# HHPrototype.net
KiCad netlist of a schematic drawn in EAGLE
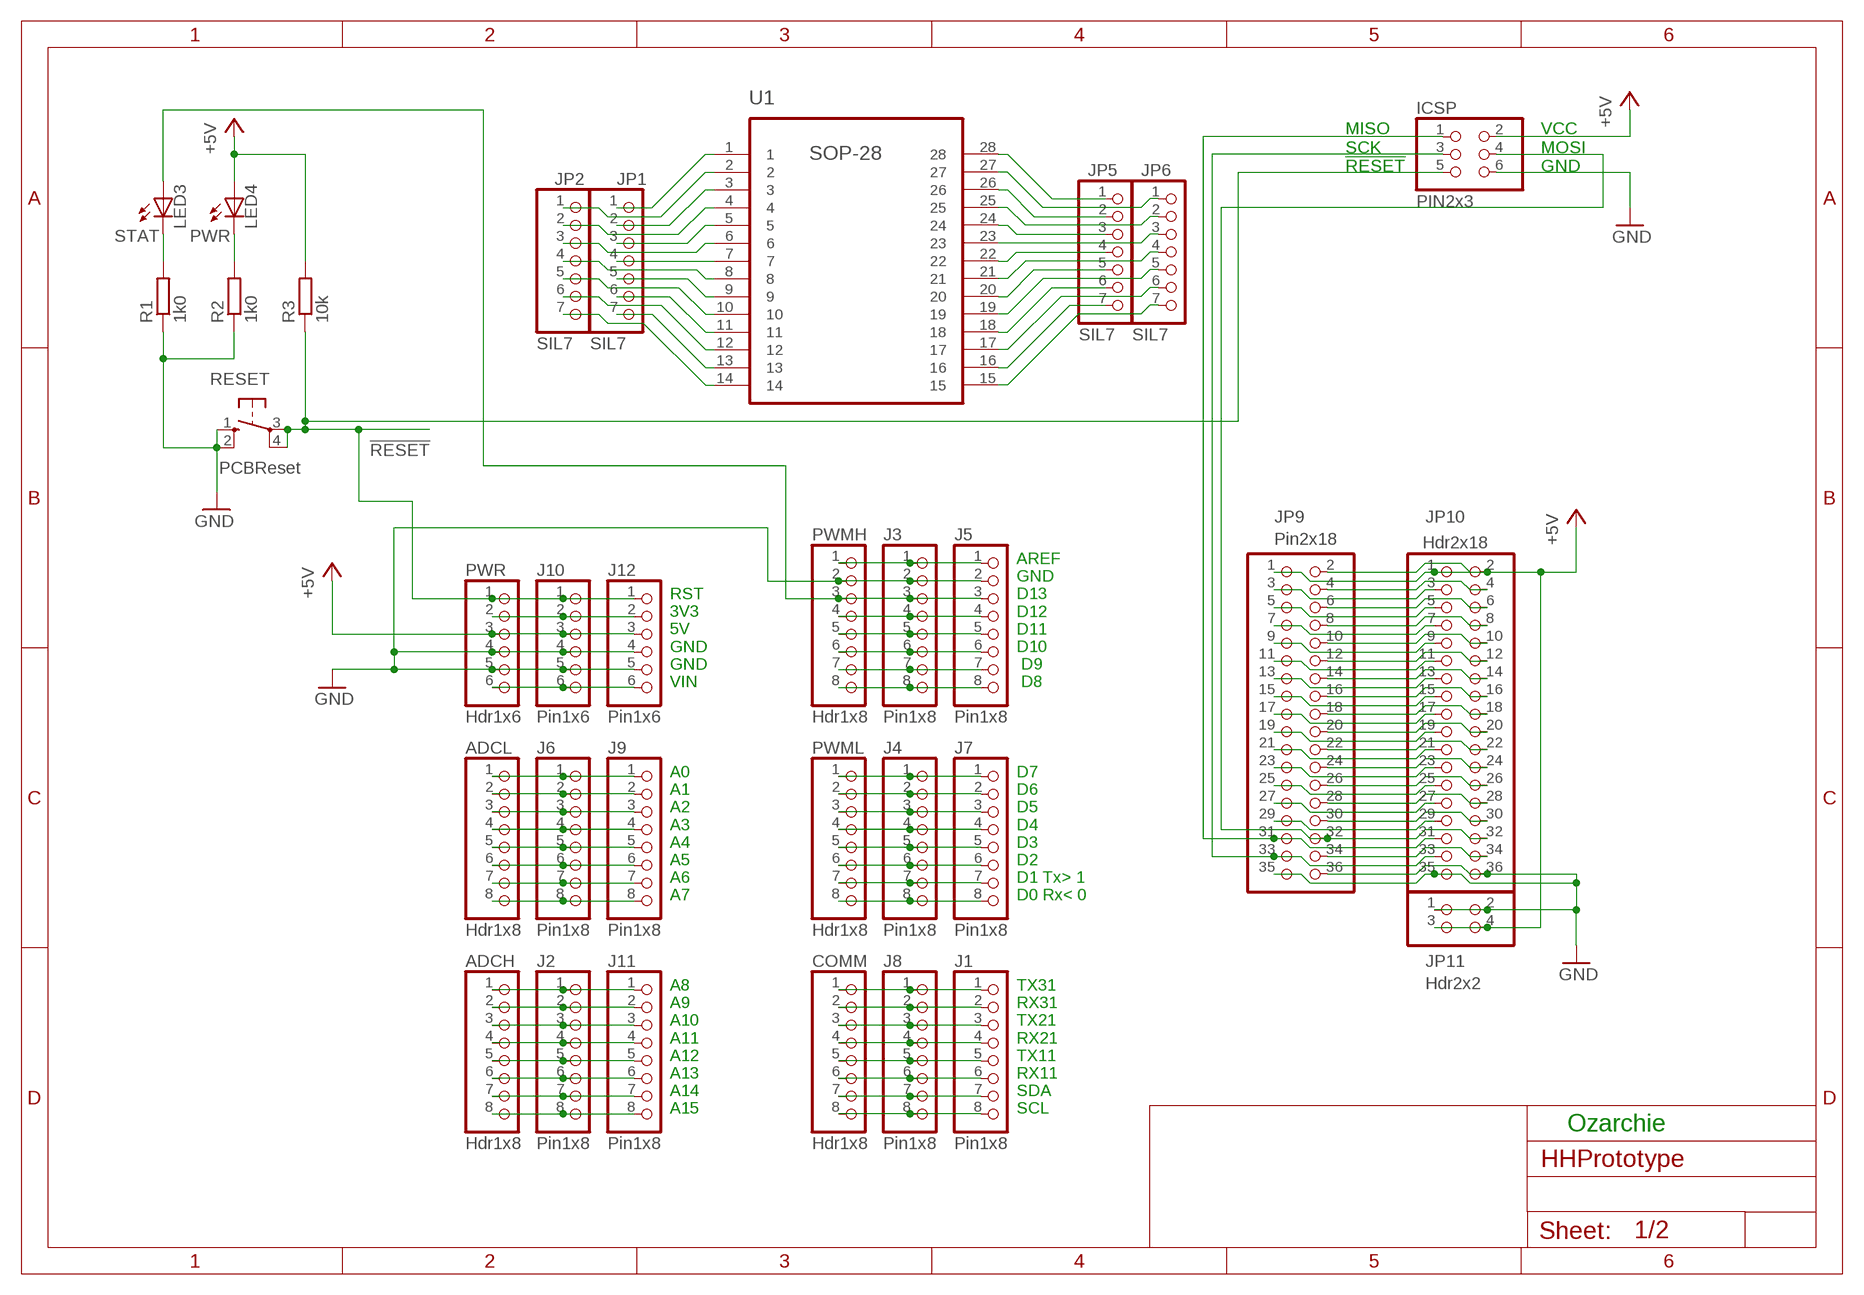
[diagram p0: schematic, sheet 1]
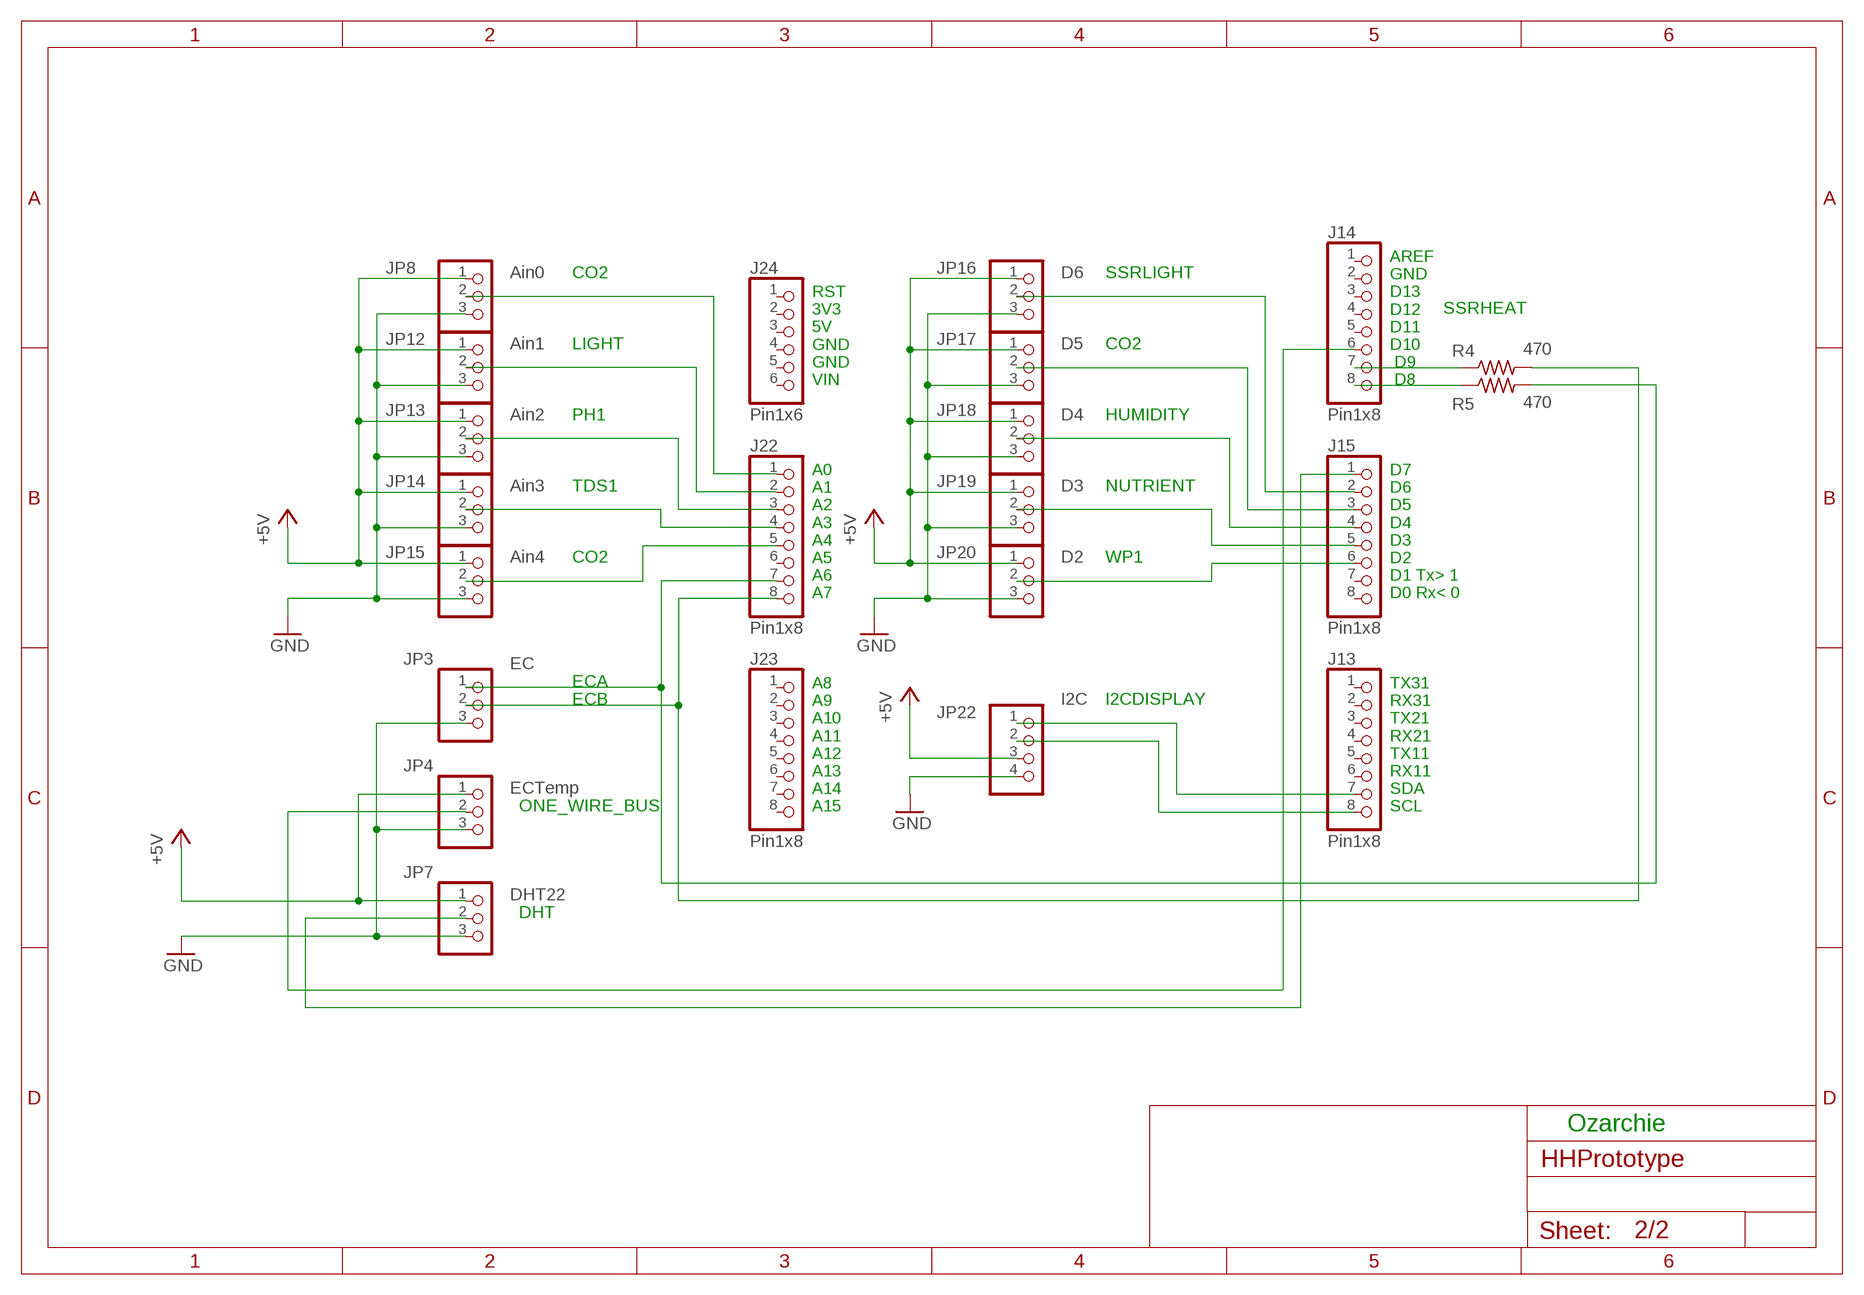
[diagram p1: schematic, sheet 2]

(export (version "E")
  (design (tool "Eeschema 10.0.6"))
  (components
    (comp (ref "ADCH")
      (value "Hdr1x8")
      (footprint "eagle-import:1X08")
      (libsource (lib "eagle-import") (part "PINHD-1X8"))
    )
    (comp (ref "ADCL")
      (value "Hdr1x8")
      (footprint "eagle-import:1X08")
      (libsource (lib "eagle-import") (part "PINHD-1X8"))
    )
    (comp (ref "COMM")
      (value "Hdr1x8")
      (footprint "eagle-import:1X08")
      (libsource (lib "eagle-import") (part "PINHD-1X8"))
    )
    (comp (ref "ICSP")
      (value "PIN2x3")
      (footprint "eagle-import:2X03")
      (libsource (lib "eagle-import") (part "PINHD-2X3"))
    )
    (comp (ref "J1")
      (value "Pin1x8")
      (footprint "eagle-import:1X08")
      (libsource (lib "eagle-import") (part "PINHD-1X8"))
    )
    (comp (ref "J2")
      (value "Pin1x8")
      (footprint "eagle-import:1X08")
      (libsource (lib "eagle-import") (part "PINHD-1X8"))
    )
    (comp (ref "J3")
      (value "Pin1x8")
      (footprint "eagle-import:1X08")
      (libsource (lib "eagle-import") (part "PINHD-1X8"))
    )
    (comp (ref "J4")
      (value "Pin1x8")
      (footprint "eagle-import:1X08")
      (libsource (lib "eagle-import") (part "PINHD-1X8"))
    )
    (comp (ref "J5")
      (value "Pin1x8")
      (footprint "eagle-import:1X08")
      (libsource (lib "eagle-import") (part "PINHD-1X8"))
    )
    (comp (ref "J6")
      (value "Pin1x8")
      (footprint "eagle-import:1X08")
      (libsource (lib "eagle-import") (part "PINHD-1X8"))
    )
    (comp (ref "J7")
      (value "Pin1x8")
      (footprint "eagle-import:1X08")
      (libsource (lib "eagle-import") (part "PINHD-1X8"))
    )
    (comp (ref "J8")
      (value "Pin1x8")
      (footprint "eagle-import:1X08")
      (libsource (lib "eagle-import") (part "PINHD-1X8"))
    )
    (comp (ref "J9")
      (value "Pin1x8")
      (footprint "eagle-import:1X08")
      (libsource (lib "eagle-import") (part "PINHD-1X8"))
    )
    (comp (ref "J10")
      (value "Pin1x6")
      (footprint "eagle-import:1X06")
      (libsource (lib "eagle-import") (part "PINHD-1X6"))
    )
    (comp (ref "J11")
      (value "Pin1x8")
      (footprint "eagle-import:1X08")
      (libsource (lib "eagle-import") (part "PINHD-1X8"))
    )
    (comp (ref "J12")
      (value "Pin1x6")
      (footprint "eagle-import:1X06")
      (libsource (lib "eagle-import") (part "PINHD-1X6"))
    )
    (comp (ref "JP1")
      (value "SIL7")
      (footprint "eagle-import:1X07")
      (libsource (lib "eagle-import") (part "PINHD-1X7"))
    )
    (comp (ref "JP2")
      (value "SIL7")
      (footprint "eagle-import:1X07")
      (libsource (lib "eagle-import") (part "PINHD-1X7"))
    )
    (comp (ref "JP5")
      (value "SIL7")
      (footprint "eagle-import:1X07")
      (libsource (lib "eagle-import") (part "PINHD-1X7"))
    )
    (comp (ref "JP6")
      (value "SIL7")
      (footprint "eagle-import:1X07")
      (libsource (lib "eagle-import") (part "PINHD-1X7"))
    )
    (comp (ref "JP9")
      (value "Pin2x18")
      (footprint "eagle-import:2X18")
      (libsource (lib "eagle-import") (part "PINHD-2X18"))
    )
    (comp (ref "JP10")
      (value "Hdr2x18")
      (footprint "eagle-import:2X18")
      (libsource (lib "eagle-import") (part "PINHD-2X18"))
    )
    (comp (ref "JP11")
      (value "Hdr2x2")
      (footprint "eagle-import:2X02")
      (libsource (lib "eagle-import") (part "PINHD-2X2"))
    )
    (comp (ref "LED3")
      (value "STAT")
      (footprint "eagle-import:CHIPLED_1206")
      (libsource (lib "eagle-import") (part "LEDCHIPLED_1206"))
    )
    (comp (ref "LED4")
      (value "PWR")
      (footprint "eagle-import:CHIPLED_1206")
      (libsource (lib "eagle-import") (part "LEDCHIPLED_1206"))
    )
    (comp (ref "PWMH")
      (value "Hdr1x8")
      (footprint "eagle-import:1X08")
      (libsource (lib "eagle-import") (part "PINHD-1X8"))
    )
    (comp (ref "PWML")
      (value "Hdr1x8")
      (footprint "eagle-import:1X08")
      (libsource (lib "eagle-import") (part "PINHD-1X8"))
    )
    (comp (ref "PWR")
      (value "Hdr1x6")
      (footprint "eagle-import:1X06")
      (libsource (lib "eagle-import") (part "PINHD-1X6"))
    )
    (comp (ref "R1")
      (value "1k0")
      (footprint "eagle-import:R0805")
      (libsource (lib "eagle-import") (part "R-EU_R0805"))
    )
    (comp (ref "R2")
      (value "1k0")
      (footprint "eagle-import:R0805")
      (libsource (lib "eagle-import") (part "R-EU_R0805"))
    )
    (comp (ref "R3")
      (value "10k")
      (footprint "eagle-import:R0805")
      (libsource (lib "eagle-import") (part "R-EU_R0805"))
    )
    (comp (ref "RESET")
      (value "PCBReset")
      (footprint "eagle-import:B3F-10XX")
      (fields (field (name "MPN") "B3F-1000"))
      (libsource (lib "eagle-import") (part "10-XX"))
    )
    (comp (ref "U1")
      (value "SOP-28")
      (footprint "eagle-import:SOP50P1030X264-28N")
      (libsource (lib "eagle-import") (part "SOP-28"))
    )
    (comp (ref "J13")
      (value "Pin1x8")
      (footprint "eagle-import:1X08")
      (libsource (lib "eagle-import") (part "PINHD-1X8"))
    )
    (comp (ref "J14")
      (value "Pin1x8")
      (footprint "eagle-import:1X08")
      (libsource (lib "eagle-import") (part "PINHD-1X8"))
    )
    (comp (ref "J15")
      (value "Pin1x8")
      (footprint "eagle-import:1X08")
      (libsource (lib "eagle-import") (part "PINHD-1X8"))
    )
    (comp (ref "J22")
      (value "Pin1x8")
      (footprint "eagle-import:1X08")
      (libsource (lib "eagle-import") (part "PINHD-1X8"))
    )
    (comp (ref "J23")
      (value "Pin1x8")
      (footprint "eagle-import:1X08")
      (libsource (lib "eagle-import") (part "PINHD-1X8"))
    )
    (comp (ref "J24")
      (value "Pin1x6")
      (footprint "eagle-import:1X06")
      (libsource (lib "eagle-import") (part "PINHD-1X6"))
    )
    (comp (ref "JP3")
      (value "EC")
      (footprint "eagle-import:1X03")
      (libsource (lib "eagle-import") (part "PINHD-1X3"))
    )
    (comp (ref "JP4")
      (value "ECTemp")
      (footprint "eagle-import:1X03")
      (libsource (lib "eagle-import") (part "PINHD-1X3"))
    )
    (comp (ref "JP7")
      (value "DHT22")
      (footprint "eagle-import:1X03")
      (libsource (lib "eagle-import") (part "PINHD-1X3"))
    )
    (comp (ref "JP8")
      (value "Ain0")
      (footprint "eagle-import:1X03")
      (libsource (lib "eagle-import") (part "PINHD-1X3"))
    )
    (comp (ref "JP12")
      (value "Ain1")
      (footprint "eagle-import:1X03")
      (libsource (lib "eagle-import") (part "PINHD-1X3"))
    )
    (comp (ref "JP13")
      (value "Ain2")
      (footprint "eagle-import:1X03")
      (libsource (lib "eagle-import") (part "PINHD-1X3"))
    )
    (comp (ref "JP14")
      (value "Ain3")
      (footprint "eagle-import:1X03")
      (libsource (lib "eagle-import") (part "PINHD-1X3"))
    )
    (comp (ref "JP15")
      (value "Ain4")
      (footprint "eagle-import:1X03")
      (libsource (lib "eagle-import") (part "PINHD-1X3"))
    )
    (comp (ref "JP16")
      (value "D6")
      (footprint "eagle-import:1X03")
      (libsource (lib "eagle-import") (part "PINHD-1X3"))
    )
    (comp (ref "JP17")
      (value "D5")
      (footprint "eagle-import:1X03")
      (libsource (lib "eagle-import") (part "PINHD-1X3"))
    )
    (comp (ref "JP18")
      (value "D4")
      (footprint "eagle-import:1X03")
      (libsource (lib "eagle-import") (part "PINHD-1X3"))
    )
    (comp (ref "JP19")
      (value "D3")
      (footprint "eagle-import:1X03")
      (libsource (lib "eagle-import") (part "PINHD-1X3"))
    )
    (comp (ref "JP20")
      (value "D2")
      (footprint "eagle-import:1X03")
      (libsource (lib "eagle-import") (part "PINHD-1X3"))
    )
    (comp (ref "JP22")
      (value "I2C")
      (footprint "eagle-import:1X04")
      (libsource (lib "eagle-import") (part "PINHD-1X4"))
    )
    (comp (ref "R4")
      (value "470")
      (footprint "eagle-import:0207_2V")
      (libsource (lib "eagle-import") (part "R-US_0207/2V"))
    )
    (comp (ref "R5")
      (value "470")
      (footprint "eagle-import:0207_2V")
      (libsource (lib "eagle-import") (part "R-US_0207/2V"))
    )
  )
  (nets
    (net (code "1") (name "+5V") (class "Default")
      (node (ref "ICSP") (pin "2") (pinfunction "2_2") (pintype "passive"))
      (node (ref "J10") (pin "3") (pinfunction "3_3") (pintype "passive"))
      (node (ref "J12") (pin "3") (pinfunction "3_3") (pintype "passive"))
      (node (ref "JP10") (pin "1") (pinfunction "1_1") (pintype "passive"))
      (node (ref "JP10") (pin "2") (pinfunction "2_2") (pintype "passive"))
      (node (ref "JP11") (pin "3") (pinfunction "3_3") (pintype "passive"))
      (node (ref "JP11") (pin "4") (pinfunction "4_4") (pintype "passive"))
      (node (ref "JP12") (pin "1") (pinfunction "1_1") (pintype "passive"))
      (node (ref "JP13") (pin "1") (pinfunction "1_1") (pintype "passive"))
      (node (ref "JP14") (pin "1") (pinfunction "1_1") (pintype "passive"))
      (node (ref "JP15") (pin "1") (pinfunction "1_1") (pintype "passive"))
      (node (ref "JP16") (pin "1") (pinfunction "1_1") (pintype "passive"))
      (node (ref "JP17") (pin "1") (pinfunction "1_1") (pintype "passive"))
      (node (ref "JP18") (pin "1") (pinfunction "1_1") (pintype "passive"))
      (node (ref "JP19") (pin "1") (pinfunction "1_1") (pintype "passive"))
      (node (ref "JP20") (pin "1") (pinfunction "1_1") (pintype "passive"))
      (node (ref "JP22") (pin "3") (pinfunction "3_3") (pintype "passive"))
      (node (ref "JP4") (pin "1") (pinfunction "1_1") (pintype "passive"))
      (node (ref "JP7") (pin "1") (pinfunction "1_1") (pintype "passive"))
      (node (ref "JP8") (pin "1") (pinfunction "1_1") (pintype "passive"))
      (node (ref "JP9") (pin "1") (pinfunction "1_1") (pintype "passive"))
      (node (ref "JP9") (pin "2") (pinfunction "2_2") (pintype "passive"))
      (node (ref "LED4") (pin "A") (pinfunction "A_A") (pintype "passive"))
      (node (ref "PWR") (pin "3") (pinfunction "3_3") (pintype "passive"))
      (node (ref "R3") (pin "2") (pinfunction "2_2") (pintype "passive"))
    )
    (net (code "2") (name "GND") (class "Default")
      (node (ref "ICSP") (pin "6") (pinfunction "6_6") (pintype "passive"))
      (node (ref "J10") (pin "4") (pinfunction "4_4") (pintype "passive"))
      (node (ref "J10") (pin "5") (pinfunction "5_5") (pintype "passive"))
      (node (ref "J12") (pin "4") (pinfunction "4_4") (pintype "passive"))
      (node (ref "J12") (pin "5") (pinfunction "5_5") (pintype "passive"))
      (node (ref "J3") (pin "2") (pinfunction "2_2") (pintype "passive"))
      (node (ref "J5") (pin "2") (pinfunction "2_2") (pintype "passive"))
      (node (ref "JP10") (pin "35") (pinfunction "35_35") (pintype "passive"))
      (node (ref "JP10") (pin "36") (pinfunction "36_36") (pintype "passive"))
      (node (ref "JP11") (pin "1") (pinfunction "1_1") (pintype "passive"))
      (node (ref "JP11") (pin "2") (pinfunction "2_2") (pintype "passive"))
      (node (ref "JP12") (pin "3") (pinfunction "3_3") (pintype "passive"))
      (node (ref "JP13") (pin "3") (pinfunction "3_3") (pintype "passive"))
      (node (ref "JP14") (pin "3") (pinfunction "3_3") (pintype "passive"))
      (node (ref "JP15") (pin "3") (pinfunction "3_3") (pintype "passive"))
      (node (ref "JP16") (pin "3") (pinfunction "3_3") (pintype "passive"))
      (node (ref "JP17") (pin "3") (pinfunction "3_3") (pintype "passive"))
      (node (ref "JP18") (pin "3") (pinfunction "3_3") (pintype "passive"))
      (node (ref "JP19") (pin "3") (pinfunction "3_3") (pintype "passive"))
      (node (ref "JP20") (pin "3") (pinfunction "3_3") (pintype "passive"))
      (node (ref "JP22") (pin "4") (pinfunction "4_4") (pintype "passive"))
      (node (ref "JP3") (pin "3") (pinfunction "3_3") (pintype "passive"))
      (node (ref "JP4") (pin "3") (pinfunction "3_3") (pintype "passive"))
      (node (ref "JP7") (pin "3") (pinfunction "3_3") (pintype "passive"))
      (node (ref "JP8") (pin "3") (pinfunction "3_3") (pintype "passive"))
      (node (ref "JP9") (pin "35") (pinfunction "35_35") (pintype "passive"))
      (node (ref "JP9") (pin "36") (pinfunction "36_36") (pintype "passive"))
      (node (ref "PWMH") (pin "2") (pinfunction "2_2") (pintype "passive"))
      (node (ref "PWR") (pin "4") (pinfunction "4_4") (pintype "passive"))
      (node (ref "PWR") (pin "5") (pinfunction "5_5") (pintype "passive"))
      (node (ref "R1") (pin "1") (pinfunction "1_1") (pintype "passive"))
      (node (ref "R2") (pin "1") (pinfunction "1_1") (pintype "passive"))
      (node (ref "RESET") (pin "1") (pinfunction "S_1") (pintype "passive"))
      (node (ref "RESET") (pin "2") (pinfunction "S1_2") (pintype "passive"))
    )
    (net (code "3") (name "Net-(ADCH-Pad1)") (class "Default")
      (node (ref "ADCH") (pin "1") (pinfunction "1_1") (pintype "passive"))
      (node (ref "J11") (pin "1") (pinfunction "1_1") (pintype "passive"))
      (node (ref "J2") (pin "1") (pinfunction "1_1") (pintype "passive"))
    )
    (net (code "4") (name "Net-(ADCH-Pad2)") (class "Default")
      (node (ref "ADCH") (pin "2") (pinfunction "2_2") (pintype "passive"))
      (node (ref "J11") (pin "2") (pinfunction "2_2") (pintype "passive"))
      (node (ref "J2") (pin "2") (pinfunction "2_2") (pintype "passive"))
    )
    (net (code "5") (name "Net-(ADCH-Pad3)") (class "Default")
      (node (ref "ADCH") (pin "3") (pinfunction "3_3") (pintype "passive"))
      (node (ref "J11") (pin "3") (pinfunction "3_3") (pintype "passive"))
      (node (ref "J2") (pin "3") (pinfunction "3_3") (pintype "passive"))
    )
    (net (code "6") (name "Net-(ADCH-Pad4)") (class "Default")
      (node (ref "ADCH") (pin "4") (pinfunction "4_4") (pintype "passive"))
      (node (ref "J11") (pin "4") (pinfunction "4_4") (pintype "passive"))
      (node (ref "J2") (pin "4") (pinfunction "4_4") (pintype "passive"))
    )
    (net (code "7") (name "Net-(ADCH-Pad5)") (class "Default")
      (node (ref "ADCH") (pin "5") (pinfunction "5_5") (pintype "passive"))
      (node (ref "J11") (pin "5") (pinfunction "5_5") (pintype "passive"))
      (node (ref "J2") (pin "5") (pinfunction "5_5") (pintype "passive"))
    )
    (net (code "8") (name "Net-(ADCH-Pad6)") (class "Default")
      (node (ref "ADCH") (pin "6") (pinfunction "6_6") (pintype "passive"))
      (node (ref "J11") (pin "6") (pinfunction "6_6") (pintype "passive"))
      (node (ref "J2") (pin "6") (pinfunction "6_6") (pintype "passive"))
    )
    (net (code "9") (name "Net-(ADCH-Pad7)") (class "Default")
      (node (ref "ADCH") (pin "7") (pinfunction "7_7") (pintype "passive"))
      (node (ref "J11") (pin "7") (pinfunction "7_7") (pintype "passive"))
      (node (ref "J2") (pin "7") (pinfunction "7_7") (pintype "passive"))
    )
    (net (code "10") (name "Net-(ADCH-Pad8)") (class "Default")
      (node (ref "ADCH") (pin "8") (pinfunction "8_8") (pintype "passive"))
      (node (ref "J11") (pin "8") (pinfunction "8_8") (pintype "passive"))
      (node (ref "J2") (pin "8") (pinfunction "8_8") (pintype "passive"))
    )
    (net (code "11") (name "Net-(ADCL-Pad1)") (class "Default")
      (node (ref "ADCL") (pin "1") (pinfunction "1_1") (pintype "passive"))
      (node (ref "J6") (pin "1") (pinfunction "1_1") (pintype "passive"))
      (node (ref "J9") (pin "1") (pinfunction "1_1") (pintype "passive"))
    )
    (net (code "12") (name "Net-(ADCL-Pad2)") (class "Default")
      (node (ref "ADCL") (pin "2") (pinfunction "2_2") (pintype "passive"))
      (node (ref "J6") (pin "2") (pinfunction "2_2") (pintype "passive"))
      (node (ref "J9") (pin "2") (pinfunction "2_2") (pintype "passive"))
    )
    (net (code "13") (name "Net-(ADCL-Pad3)") (class "Default")
      (node (ref "ADCL") (pin "3") (pinfunction "3_3") (pintype "passive"))
      (node (ref "J6") (pin "3") (pinfunction "3_3") (pintype "passive"))
      (node (ref "J9") (pin "3") (pinfunction "3_3") (pintype "passive"))
    )
    (net (code "14") (name "Net-(ADCL-Pad4)") (class "Default")
      (node (ref "ADCL") (pin "4") (pinfunction "4_4") (pintype "passive"))
      (node (ref "J6") (pin "4") (pinfunction "4_4") (pintype "passive"))
      (node (ref "J9") (pin "4") (pinfunction "4_4") (pintype "passive"))
    )
    (net (code "15") (name "Net-(ADCL-Pad5)") (class "Default")
      (node (ref "ADCL") (pin "5") (pinfunction "5_5") (pintype "passive"))
      (node (ref "J6") (pin "5") (pinfunction "5_5") (pintype "passive"))
      (node (ref "J9") (pin "5") (pinfunction "5_5") (pintype "passive"))
    )
    (net (code "16") (name "Net-(ADCL-Pad6)") (class "Default")
      (node (ref "ADCL") (pin "6") (pinfunction "6_6") (pintype "passive"))
      (node (ref "J6") (pin "6") (pinfunction "6_6") (pintype "passive"))
      (node (ref "J9") (pin "6") (pinfunction "6_6") (pintype "passive"))
    )
    (net (code "17") (name "Net-(ADCL-Pad7)") (class "Default")
      (node (ref "ADCL") (pin "7") (pinfunction "7_7") (pintype "passive"))
      (node (ref "J6") (pin "7") (pinfunction "7_7") (pintype "passive"))
      (node (ref "J9") (pin "7") (pinfunction "7_7") (pintype "passive"))
    )
    (net (code "18") (name "Net-(ADCL-Pad8)") (class "Default")
      (node (ref "ADCL") (pin "8") (pinfunction "8_8") (pintype "passive"))
      (node (ref "J6") (pin "8") (pinfunction "8_8") (pintype "passive"))
      (node (ref "J9") (pin "8") (pinfunction "8_8") (pintype "passive"))
    )
    (net (code "19") (name "Net-(COMM-Pad1)") (class "Default")
      (node (ref "COMM") (pin "1") (pinfunction "1_1") (pintype "passive"))
      (node (ref "J1") (pin "1") (pinfunction "1_1") (pintype "passive"))
      (node (ref "J8") (pin "1") (pinfunction "1_1") (pintype "passive"))
    )
    (net (code "20") (name "Net-(COMM-Pad2)") (class "Default")
      (node (ref "COMM") (pin "2") (pinfunction "2_2") (pintype "passive"))
      (node (ref "J1") (pin "2") (pinfunction "2_2") (pintype "passive"))
      (node (ref "J8") (pin "2") (pinfunction "2_2") (pintype "passive"))
    )
    (net (code "21") (name "Net-(COMM-Pad3)") (class "Default")
      (node (ref "COMM") (pin "3") (pinfunction "3_3") (pintype "passive"))
      (node (ref "J1") (pin "3") (pinfunction "3_3") (pintype "passive"))
      (node (ref "J8") (pin "3") (pinfunction "3_3") (pintype "passive"))
    )
    (net (code "22") (name "Net-(COMM-Pad4)") (class "Default")
      (node (ref "COMM") (pin "4") (pinfunction "4_4") (pintype "passive"))
      (node (ref "J1") (pin "4") (pinfunction "4_4") (pintype "passive"))
      (node (ref "J8") (pin "4") (pinfunction "4_4") (pintype "passive"))
    )
    (net (code "23") (name "Net-(COMM-Pad5)") (class "Default")
      (node (ref "COMM") (pin "5") (pinfunction "5_5") (pintype "passive"))
      (node (ref "J1") (pin "5") (pinfunction "5_5") (pintype "passive"))
      (node (ref "J8") (pin "5") (pinfunction "5_5") (pintype "passive"))
    )
    (net (code "24") (name "Net-(COMM-Pad6)") (class "Default")
      (node (ref "COMM") (pin "6") (pinfunction "6_6") (pintype "passive"))
      (node (ref "J1") (pin "6") (pinfunction "6_6") (pintype "passive"))
      (node (ref "J8") (pin "6") (pinfunction "6_6") (pintype "passive"))
    )
    (net (code "25") (name "Net-(COMM-Pad7)") (class "Default")
      (node (ref "COMM") (pin "7") (pinfunction "7_7") (pintype "passive"))
      (node (ref "J1") (pin "7") (pinfunction "7_7") (pintype "passive"))
      (node (ref "J8") (pin "7") (pinfunction "7_7") (pintype "passive"))
    )
    (net (code "26") (name "Net-(COMM-Pad8)") (class "Default")
      (node (ref "COMM") (pin "8") (pinfunction "8_8") (pintype "passive"))
      (node (ref "J1") (pin "8") (pinfunction "8_8") (pintype "passive"))
      (node (ref "J8") (pin "8") (pinfunction "8_8") (pintype "passive"))
    )
    (net (code "27") (name "Net-(ICSP-Pad1)") (class "Default")
      (node (ref "ICSP") (pin "1") (pinfunction "1_1") (pintype "passive"))
      (node (ref "JP10") (pin "31") (pinfunction "31_31") (pintype "passive"))
      (node (ref "JP9") (pin "31") (pinfunction "31_31") (pintype "passive"))
    )
    (net (code "28") (name "Net-(ICSP-Pad3)") (class "Default")
      (node (ref "ICSP") (pin "3") (pinfunction "3_3") (pintype "passive"))
      (node (ref "JP10") (pin "33") (pinfunction "33_33") (pintype "passive"))
      (node (ref "JP9") (pin "33") (pinfunction "33_33") (pintype "passive"))
    )
    (net (code "29") (name "Net-(ICSP-Pad4)") (class "Default")
      (node (ref "ICSP") (pin "4") (pinfunction "4_4") (pintype "passive"))
      (node (ref "JP10") (pin "32") (pinfunction "32_32") (pintype "passive"))
      (node (ref "JP9") (pin "32") (pinfunction "32_32") (pintype "passive"))
    )
    (net (code "30") (name "Net-(J3-Pad1)") (class "Default")
      (node (ref "J3") (pin "1") (pinfunction "1_1") (pintype "passive"))
      (node (ref "J5") (pin "1") (pinfunction "1_1") (pintype "passive"))
      (node (ref "PWMH") (pin "1") (pinfunction "1_1") (pintype "passive"))
    )
    (net (code "31") (name "Net-(J3-Pad3)") (class "Default")
      (node (ref "J3") (pin "3") (pinfunction "3_3") (pintype "passive"))
      (node (ref "J5") (pin "3") (pinfunction "3_3") (pintype "passive"))
      (node (ref "LED3") (pin "A") (pinfunction "A_A") (pintype "passive"))
      (node (ref "PWMH") (pin "3") (pinfunction "3_3") (pintype "passive"))
    )
    (net (code "32") (name "Net-(J3-Pad4)") (class "Default")
      (node (ref "J3") (pin "4") (pinfunction "4_4") (pintype "passive"))
      (node (ref "J5") (pin "4") (pinfunction "4_4") (pintype "passive"))
      (node (ref "PWMH") (pin "4") (pinfunction "4_4") (pintype "passive"))
    )
    (net (code "33") (name "Net-(J3-Pad5)") (class "Default")
      (node (ref "J3") (pin "5") (pinfunction "5_5") (pintype "passive"))
      (node (ref "J5") (pin "5") (pinfunction "5_5") (pintype "passive"))
      (node (ref "PWMH") (pin "5") (pinfunction "5_5") (pintype "passive"))
    )
    (net (code "34") (name "Net-(J3-Pad6)") (class "Default")
      (node (ref "J3") (pin "6") (pinfunction "6_6") (pintype "passive"))
      (node (ref "J5") (pin "6") (pinfunction "6_6") (pintype "passive"))
      (node (ref "PWMH") (pin "6") (pinfunction "6_6") (pintype "passive"))
    )
    (net (code "35") (name "Net-(J3-Pad7)") (class "Default")
      (node (ref "J3") (pin "7") (pinfunction "7_7") (pintype "passive"))
      (node (ref "J5") (pin "7") (pinfunction "7_7") (pintype "passive"))
      (node (ref "PWMH") (pin "7") (pinfunction "7_7") (pintype "passive"))
    )
    (net (code "36") (name "Net-(J3-Pad8)") (class "Default")
      (node (ref "J3") (pin "8") (pinfunction "8_8") (pintype "passive"))
      (node (ref "J5") (pin "8") (pinfunction "8_8") (pintype "passive"))
      (node (ref "PWMH") (pin "8") (pinfunction "8_8") (pintype "passive"))
    )
    (net (code "37") (name "Net-(J4-Pad1)") (class "Default")
      (node (ref "J4") (pin "1") (pinfunction "1_1") (pintype "passive"))
      (node (ref "J7") (pin "1") (pinfunction "1_1") (pintype "passive"))
      (node (ref "PWML") (pin "1") (pinfunction "1_1") (pintype "passive"))
    )
    (net (code "38") (name "Net-(J4-Pad2)") (class "Default")
      (node (ref "J4") (pin "2") (pinfunction "2_2") (pintype "passive"))
      (node (ref "J7") (pin "2") (pinfunction "2_2") (pintype "passive"))
      (node (ref "PWML") (pin "2") (pinfunction "2_2") (pintype "passive"))
    )
    (net (code "39") (name "Net-(J4-Pad3)") (class "Default")
      (node (ref "J4") (pin "3") (pinfunction "3_3") (pintype "passive"))
      (node (ref "J7") (pin "3") (pinfunction "3_3") (pintype "passive"))
      (node (ref "PWML") (pin "3") (pinfunction "3_3") (pintype "passive"))
    )
    (net (code "40") (name "Net-(J4-Pad4)") (class "Default")
      (node (ref "J4") (pin "4") (pinfunction "4_4") (pintype "passive"))
      (node (ref "J7") (pin "4") (pinfunction "4_4") (pintype "passive"))
      (node (ref "PWML") (pin "4") (pinfunction "4_4") (pintype "passive"))
    )
    (net (code "41") (name "Net-(J4-Pad5)") (class "Default")
      (node (ref "J4") (pin "5") (pinfunction "5_5") (pintype "passive"))
      (node (ref "J7") (pin "5") (pinfunction "5_5") (pintype "passive"))
      (node (ref "PWML") (pin "5") (pinfunction "5_5") (pintype "passive"))
    )
    (net (code "42") (name "Net-(J4-Pad6)") (class "Default")
      (node (ref "J4") (pin "6") (pinfunction "6_6") (pintype "passive"))
      (node (ref "J7") (pin "6") (pinfunction "6_6") (pintype "passive"))
      (node (ref "PWML") (pin "6") (pinfunction "6_6") (pintype "passive"))
    )
    (net (code "43") (name "Net-(J4-Pad7)") (class "Default")
      (node (ref "J4") (pin "7") (pinfunction "7_7") (pintype "passive"))
      (node (ref "J7") (pin "7") (pinfunction "7_7") (pintype "passive"))
      (node (ref "PWML") (pin "7") (pinfunction "7_7") (pintype "passive"))
    )
    (net (code "44") (name "Net-(J4-Pad8)") (class "Default")
      (node (ref "J4") (pin "8") (pinfunction "8_8") (pintype "passive"))
      (node (ref "J7") (pin "8") (pinfunction "8_8") (pintype "passive"))
      (node (ref "PWML") (pin "8") (pinfunction "8_8") (pintype "passive"))
    )
    (net (code "45") (name "Net-(J10-Pad2)") (class "Default")
      (node (ref "J10") (pin "2") (pinfunction "2_2") (pintype "passive"))
      (node (ref "J12") (pin "2") (pinfunction "2_2") (pintype "passive"))
      (node (ref "PWR") (pin "2") (pinfunction "2_2") (pintype "passive"))
    )
    (net (code "46") (name "Net-(J10-Pad6)") (class "Default")
      (node (ref "J10") (pin "6") (pinfunction "6_6") (pintype "passive"))
      (node (ref "J12") (pin "6") (pinfunction "6_6") (pintype "passive"))
      (node (ref "PWR") (pin "6") (pinfunction "6_6") (pintype "passive"))
    )
    (net (code "47") (name "Net-(J13-Pad7)") (class "Default")
      (node (ref "J13") (pin "7") (pinfunction "7_7") (pintype "passive"))
      (node (ref "JP22") (pin "1") (pinfunction "1_1") (pintype "passive"))
    )
    (net (code "48") (name "Net-(J13-Pad8)") (class "Default")
      (node (ref "J13") (pin "8") (pinfunction "8_8") (pintype "passive"))
      (node (ref "JP22") (pin "2") (pinfunction "2_2") (pintype "passive"))
    )
    (net (code "49") (name "Net-(J14-Pad6)") (class "Default")
      (node (ref "J14") (pin "6") (pinfunction "6_6") (pintype "passive"))
      (node (ref "JP4") (pin "2") (pinfunction "2_2") (pintype "passive"))
    )
    (net (code "50") (name "Net-(J14-Pad7)") (class "Default")
      (node (ref "J14") (pin "7") (pinfunction "7_7") (pintype "passive"))
      (node (ref "R4") (pin "1") (pinfunction "1_1") (pintype "passive"))
    )
    (net (code "51") (name "Net-(J14-Pad8)") (class "Default")
      (node (ref "J14") (pin "8") (pinfunction "8_8") (pintype "passive"))
      (node (ref "R5") (pin "1") (pinfunction "1_1") (pintype "passive"))
    )
    (net (code "52") (name "Net-(J15-Pad1)") (class "Default")
      (node (ref "J15") (pin "1") (pinfunction "1_1") (pintype "passive"))
      (node (ref "JP7") (pin "2") (pinfunction "2_2") (pintype "passive"))
    )
    (net (code "53") (name "Net-(J15-Pad2)") (class "Default")
      (node (ref "J15") (pin "2") (pinfunction "2_2") (pintype "passive"))
      (node (ref "JP16") (pin "2") (pinfunction "2_2") (pintype "passive"))
    )
    (net (code "54") (name "Net-(J15-Pad3)") (class "Default")
      (node (ref "J15") (pin "3") (pinfunction "3_3") (pintype "passive"))
      (node (ref "JP17") (pin "2") (pinfunction "2_2") (pintype "passive"))
    )
    (net (code "55") (name "Net-(J15-Pad4)") (class "Default")
      (node (ref "J15") (pin "4") (pinfunction "4_4") (pintype "passive"))
      (node (ref "JP18") (pin "2") (pinfunction "2_2") (pintype "passive"))
    )
    (net (code "56") (name "Net-(J15-Pad5)") (class "Default")
      (node (ref "J15") (pin "5") (pinfunction "5_5") (pintype "passive"))
      (node (ref "JP19") (pin "2") (pinfunction "2_2") (pintype "passive"))
    )
    (net (code "57") (name "Net-(J15-Pad6)") (class "Default")
      (node (ref "J15") (pin "6") (pinfunction "6_6") (pintype "passive"))
      (node (ref "JP20") (pin "2") (pinfunction "2_2") (pintype "passive"))
    )
    (net (code "58") (name "Net-(J22-Pad1)") (class "Default")
      (node (ref "J22") (pin "1") (pinfunction "1_1") (pintype "passive"))
      (node (ref "JP8") (pin "2") (pinfunction "2_2") (pintype "passive"))
    )
    (net (code "59") (name "Net-(J22-Pad2)") (class "Default")
      (node (ref "J22") (pin "2") (pinfunction "2_2") (pintype "passive"))
      (node (ref "JP12") (pin "2") (pinfunction "2_2") (pintype "passive"))
    )
    (net (code "60") (name "Net-(J22-Pad3)") (class "Default")
      (node (ref "J22") (pin "3") (pinfunction "3_3") (pintype "passive"))
      (node (ref "JP13") (pin "2") (pinfunction "2_2") (pintype "passive"))
    )
    (net (code "61") (name "Net-(J22-Pad4)") (class "Default")
      (node (ref "J22") (pin "4") (pinfunction "4_4") (pintype "passive"))
      (node (ref "JP14") (pin "2") (pinfunction "2_2") (pintype "passive"))
    )
    (net (code "62") (name "Net-(J22-Pad5)") (class "Default")
      (node (ref "J22") (pin "5") (pinfunction "5_5") (pintype "passive"))
      (node (ref "JP15") (pin "2") (pinfunction "2_2") (pintype "passive"))
    )
    (net (code "63") (name "Net-(J22-Pad7)") (class "Default")
      (node (ref "J22") (pin "7") (pinfunction "7_7") (pintype "passive"))
      (node (ref "JP3") (pin "1") (pinfunction "1_1") (pintype "passive"))
      (node (ref "R5") (pin "2") (pinfunction "2_2") (pintype "passive"))
    )
    (net (code "64") (name "Net-(J22-Pad8)") (class "Default")
      (node (ref "J22") (pin "8") (pinfunction "8_8") (pintype "passive"))
      (node (ref "JP3") (pin "2") (pinfunction "2_2") (pintype "passive"))
      (node (ref "R4") (pin "2") (pinfunction "2_2") (pintype "passive"))
    )
    (net (code "65") (name "Net-(JP1-Pad1)") (class "Default")
      (node (ref "JP1") (pin "1") (pinfunction "1_1") (pintype "passive"))
      (node (ref "U1") (pin "1") (pinfunction "1_1") (pintype "bidirectional"))
    )
    (net (code "66") (name "Net-(JP1-Pad2)") (class "Default")
      (node (ref "JP1") (pin "2") (pinfunction "2_2") (pintype "passive"))
      (node (ref "U1") (pin "3") (pinfunction "3_3") (pintype "bidirectional"))
    )
    (net (code "67") (name "Net-(JP1-Pad3)") (class "Default")
      (node (ref "JP1") (pin "3") (pinfunction "3_3") (pintype "passive"))
      (node (ref "U1") (pin "5") (pinfunction "5_5") (pintype "bidirectional"))
    )
    (net (code "68") (name "Net-(JP1-Pad4)") (class "Default")
      (node (ref "JP1") (pin "4") (pinfunction "4_4") (pintype "passive"))
      (node (ref "U1") (pin "7") (pinfunction "7_7") (pintype "bidirectional"))
    )
    (net (code "69") (name "Net-(JP1-Pad5)") (class "Default")
      (node (ref "JP1") (pin "5") (pinfunction "5_5") (pintype "passive"))
      (node (ref "U1") (pin "9") (pinfunction "9_9") (pintype "bidirectional"))
    )
    (net (code "70") (name "Net-(JP1-Pad6)") (class "Default")
      (node (ref "JP1") (pin "6") (pinfunction "6_6") (pintype "passive"))
      (node (ref "U1") (pin "11") (pinfunction "11_11") (pintype "bidirectional"))
    )
    (net (code "71") (name "Net-(JP1-Pad7)") (class "Default")
      (node (ref "JP1") (pin "7") (pinfunction "7_7") (pintype "passive"))
      (node (ref "U1") (pin "13") (pinfunction "13_13") (pintype "bidirectional"))
    )
    (net (code "72") (name "Net-(JP2-Pad1)") (class "Default")
      (node (ref "JP2") (pin "1") (pinfunction "1_1") (pintype "passive"))
      (node (ref "U1") (pin "2") (pinfunction "2_2") (pintype "bidirectional"))
    )
    (net (code "73") (name "Net-(JP2-Pad2)") (class "Default")
      (node (ref "JP2") (pin "2") (pinfunction "2_2") (pintype "passive"))
      (node (ref "U1") (pin "4") (pinfunction "4_4") (pintype "bidirectional"))
    )
    (net (code "74") (name "Net-(JP2-Pad3)") (class "Default")
      (node (ref "JP2") (pin "3") (pinfunction "3_3") (pintype "passive"))
      (node (ref "U1") (pin "6") (pinfunction "6_6") (pintype "bidirectional"))
    )
    (net (code "75") (name "Net-(JP2-Pad4)") (class "Default")
      (node (ref "JP2") (pin "4") (pinfunction "4_4") (pintype "passive"))
      (node (ref "U1") (pin "8") (pinfunction "8_8") (pintype "bidirectional"))
    )
    (net (code "76") (name "Net-(JP2-Pad5)") (class "Default")
      (node (ref "JP2") (pin "5") (pinfunction "5_5") (pintype "passive"))
      (node (ref "U1") (pin "10") (pinfunction "10_10") (pintype "bidirectional"))
    )
    (net (code "77") (name "Net-(JP2-Pad6)") (class "Default")
      (node (ref "JP2") (pin "6") (pinfunction "6_6") (pintype "passive"))
      (node (ref "U1") (pin "12") (pinfunction "12_12") (pintype "bidirectional"))
    )
    (net (code "78") (name "Net-(JP2-Pad7)") (class "Default")
      (node (ref "JP2") (pin "7") (pinfunction "7_7") (pintype "passive"))
      (node (ref "U1") (pin "14") (pinfunction "14_14") (pintype "bidirectional"))
    )
    (net (code "79") (name "Net-(JP5-Pad1)") (class "Default")
      (node (ref "JP5") (pin "1") (pinfunction "1_1") (pintype "passive"))
      (node (ref "U1") (pin "28") (pinfunction "28_28") (pintype "bidirectional"))
    )
    (net (code "80") (name "Net-(JP5-Pad2)") (class "Default")
      (node (ref "JP5") (pin "2") (pinfunction "2_2") (pintype "passive"))
      (node (ref "U1") (pin "26") (pinfunction "26_26") (pintype "bidirectional"))
    )
    (net (code "81") (name "Net-(JP5-Pad3)") (class "Default")
      (node (ref "JP5") (pin "3") (pinfunction "3_3") (pintype "passive"))
      (node (ref "U1") (pin "24") (pinfunction "24_24") (pintype "bidirectional"))
    )
    (net (code "82") (name "Net-(JP5-Pad4)") (class "Default")
      (node (ref "JP5") (pin "4") (pinfunction "4_4") (pintype "passive"))
      (node (ref "U1") (pin "22") (pinfunction "22_22") (pintype "bidirectional"))
    )
    (net (code "83") (name "Net-(JP5-Pad5)") (class "Default")
      (node (ref "JP5") (pin "5") (pinfunction "5_5") (pintype "passive"))
      (node (ref "U1") (pin "20") (pinfunction "20_20") (pintype "bidirectional"))
    )
    (net (code "84") (name "Net-(JP5-Pad6)") (class "Default")
      (node (ref "JP5") (pin "6") (pinfunction "6_6") (pintype "passive"))
      (node (ref "U1") (pin "18") (pinfunction "18_18") (pintype "bidirectional"))
    )
    (net (code "85") (name "Net-(JP5-Pad7)") (class "Default")
      (node (ref "JP5") (pin "7") (pinfunction "7_7") (pintype "passive"))
      (node (ref "U1") (pin "16") (pinfunction "16_16") (pintype "bidirectional"))
    )
    (net (code "86") (name "Net-(JP6-Pad1)") (class "Default")
      (node (ref "JP6") (pin "1") (pinfunction "1_1") (pintype "passive"))
      (node (ref "U1") (pin "27") (pinfunction "27_27") (pintype "bidirectional"))
    )
    (net (code "87") (name "Net-(JP6-Pad2)") (class "Default")
      (node (ref "JP6") (pin "2") (pinfunction "2_2") (pintype "passive"))
      (node (ref "U1") (pin "25") (pinfunction "25_25") (pintype "bidirectional"))
    )
    (net (code "88") (name "Net-(JP6-Pad3)") (class "Default")
      (node (ref "JP6") (pin "3") (pinfunction "3_3") (pintype "passive"))
      (node (ref "U1") (pin "23") (pinfunction "23_23") (pintype "bidirectional"))
    )
    (net (code "89") (name "Net-(JP6-Pad4)") (class "Default")
      (node (ref "JP6") (pin "4") (pinfunction "4_4") (pintype "passive"))
      (node (ref "U1") (pin "21") (pinfunction "21_21") (pintype "bidirectional"))
    )
    (net (code "90") (name "Net-(JP6-Pad5)") (class "Default")
      (node (ref "JP6") (pin "5") (pinfunction "5_5") (pintype "passive"))
      (node (ref "U1") (pin "19") (pinfunction "19_19") (pintype "bidirectional"))
    )
    (net (code "91") (name "Net-(JP6-Pad6)") (class "Default")
      (node (ref "JP6") (pin "6") (pinfunction "6_6") (pintype "passive"))
      (node (ref "U1") (pin "17") (pinfunction "17_17") (pintype "bidirectional"))
    )
    (net (code "92") (name "Net-(JP6-Pad7)") (class "Default")
      (node (ref "JP6") (pin "7") (pinfunction "7_7") (pintype "passive"))
      (node (ref "U1") (pin "15") (pinfunction "15_15") (pintype "bidirectional"))
    )
    (net (code "93") (name "Net-(JP10-Pad3)") (class "Default")
      (node (ref "JP10") (pin "3") (pinfunction "3_3") (pintype "passive"))
      (node (ref "JP9") (pin "3") (pinfunction "3_3") (pintype "passive"))
    )
    (net (code "94") (name "Net-(JP10-Pad4)") (class "Default")
      (node (ref "JP10") (pin "4") (pinfunction "4_4") (pintype "passive"))
      (node (ref "JP9") (pin "4") (pinfunction "4_4") (pintype "passive"))
    )
    (net (code "95") (name "Net-(JP10-Pad5)") (class "Default")
      (node (ref "JP10") (pin "5") (pinfunction "5_5") (pintype "passive"))
      (node (ref "JP9") (pin "5") (pinfunction "5_5") (pintype "passive"))
    )
    (net (code "96") (name "Net-(JP10-Pad6)") (class "Default")
      (node (ref "JP10") (pin "6") (pinfunction "6_6") (pintype "passive"))
      (node (ref "JP9") (pin "6") (pinfunction "6_6") (pintype "passive"))
    )
    (net (code "97") (name "Net-(JP10-Pad7)") (class "Default")
      (node (ref "JP10") (pin "7") (pinfunction "7_7") (pintype "passive"))
      (node (ref "JP9") (pin "7") (pinfunction "7_7") (pintype "passive"))
    )
    (net (code "98") (name "Net-(JP10-Pad8)") (class "Default")
      (node (ref "JP10") (pin "8") (pinfunction "8_8") (pintype "passive"))
      (node (ref "JP9") (pin "8") (pinfunction "8_8") (pintype "passive"))
    )
    (net (code "99") (name "Net-(JP10-Pad9)") (class "Default")
      (node (ref "JP10") (pin "9") (pinfunction "9_9") (pintype "passive"))
      (node (ref "JP9") (pin "9") (pinfunction "9_9") (pintype "passive"))
    )
    (net (code "100") (name "Net-(JP10-Pad10)") (class "Default")
      (node (ref "JP10") (pin "10") (pinfunction "10_10") (pintype "passive"))
      (node (ref "JP9") (pin "10") (pinfunction "10_10") (pintype "passive"))
    )
    (net (code "101") (name "Net-(JP10-Pad11)") (class "Default")
      (node (ref "JP10") (pin "11") (pinfunction "11_11") (pintype "passive"))
      (node (ref "JP9") (pin "11") (pinfunction "11_11") (pintype "passive"))
    )
    (net (code "102") (name "Net-(JP10-Pad12)") (class "Default")
      (node (ref "JP10") (pin "12") (pinfunction "12_12") (pintype "passive"))
      (node (ref "JP9") (pin "12") (pinfunction "12_12") (pintype "passive"))
    )
    (net (code "103") (name "Net-(JP10-Pad13)") (class "Default")
      (node (ref "JP10") (pin "13") (pinfunction "13_13") (pintype "passive"))
      (node (ref "JP9") (pin "13") (pinfunction "13_13") (pintype "passive"))
    )
    (net (code "104") (name "Net-(JP10-Pad14)") (class "Default")
      (node (ref "JP10") (pin "14") (pinfunction "14_14") (pintype "passive"))
      (node (ref "JP9") (pin "14") (pinfunction "14_14") (pintype "passive"))
    )
    (net (code "105") (name "Net-(JP10-Pad15)") (class "Default")
      (node (ref "JP10") (pin "15") (pinfunction "15_15") (pintype "passive"))
      (node (ref "JP9") (pin "15") (pinfunction "15_15") (pintype "passive"))
    )
    (net (code "106") (name "Net-(JP10-Pad16)") (class "Default")
      (node (ref "JP10") (pin "16") (pinfunction "16_16") (pintype "passive"))
      (node (ref "JP9") (pin "16") (pinfunction "16_16") (pintype "passive"))
    )
    (net (code "107") (name "Net-(JP10-Pad17)") (class "Default")
      (node (ref "JP10") (pin "17") (pinfunction "17_17") (pintype "passive"))
      (node (ref "JP9") (pin "17") (pinfunction "17_17") (pintype "passive"))
    )
    (net (code "108") (name "Net-(JP10-Pad18)") (class "Default")
      (node (ref "JP10") (pin "18") (pinfunction "18_18") (pintype "passive"))
      (node (ref "JP9") (pin "18") (pinfunction "18_18") (pintype "passive"))
    )
    (net (code "109") (name "Net-(JP10-Pad19)") (class "Default")
      (node (ref "JP10") (pin "19") (pinfunction "19_19") (pintype "passive"))
      (node (ref "JP9") (pin "19") (pinfunction "19_19") (pintype "passive"))
    )
    (net (code "110") (name "Net-(JP10-Pad20)") (class "Default")
      (node (ref "JP10") (pin "20") (pinfunction "20_20") (pintype "passive"))
      (node (ref "JP9") (pin "20") (pinfunction "20_20") (pintype "passive"))
    )
    (net (code "111") (name "Net-(JP10-Pad21)") (class "Default")
      (node (ref "JP10") (pin "21") (pinfunction "21_21") (pintype "passive"))
      (node (ref "JP9") (pin "21") (pinfunction "21_21") (pintype "passive"))
    )
    (net (code "112") (name "Net-(JP10-Pad22)") (class "Default")
      (node (ref "JP10") (pin "22") (pinfunction "22_22") (pintype "passive"))
      (node (ref "JP9") (pin "22") (pinfunction "22_22") (pintype "passive"))
    )
    (net (code "113") (name "Net-(JP10-Pad23)") (class "Default")
      (node (ref "JP10") (pin "23") (pinfunction "23_23") (pintype "passive"))
      (node (ref "JP9") (pin "23") (pinfunction "23_23") (pintype "passive"))
    )
    (net (code "114") (name "Net-(JP10-Pad24)") (class "Default")
      (node (ref "JP10") (pin "24") (pinfunction "24_24") (pintype "passive"))
      (node (ref "JP9") (pin "24") (pinfunction "24_24") (pintype "passive"))
    )
    (net (code "115") (name "Net-(JP10-Pad25)") (class "Default")
      (node (ref "JP10") (pin "25") (pinfunction "25_25") (pintype "passive"))
      (node (ref "JP9") (pin "25") (pinfunction "25_25") (pintype "passive"))
    )
    (net (code "116") (name "Net-(JP10-Pad26)") (class "Default")
      (node (ref "JP10") (pin "26") (pinfunction "26_26") (pintype "passive"))
      (node (ref "JP9") (pin "26") (pinfunction "26_26") (pintype "passive"))
    )
    (net (code "117") (name "Net-(JP10-Pad27)") (class "Default")
      (node (ref "JP10") (pin "27") (pinfunction "27_27") (pintype "passive"))
      (node (ref "JP9") (pin "27") (pinfunction "27_27") (pintype "passive"))
    )
    (net (code "118") (name "Net-(JP10-Pad28)") (class "Default")
      (node (ref "JP10") (pin "28") (pinfunction "28_28") (pintype "passive"))
      (node (ref "JP9") (pin "28") (pinfunction "28_28") (pintype "passive"))
    )
    (net (code "119") (name "Net-(JP10-Pad29)") (class "Default")
      (node (ref "JP10") (pin "29") (pinfunction "29_29") (pintype "passive"))
      (node (ref "JP9") (pin "29") (pinfunction "29_29") (pintype "passive"))
    )
    (net (code "120") (name "Net-(JP10-Pad30)") (class "Default")
      (node (ref "JP10") (pin "30") (pinfunction "30_30") (pintype "passive"))
      (node (ref "JP9") (pin "30") (pinfunction "30_30") (pintype "passive"))
    )
    (net (code "121") (name "Net-(JP10-Pad34)") (class "Default")
      (node (ref "JP10") (pin "34") (pinfunction "34_34") (pintype "passive"))
      (node (ref "JP9") (pin "34") (pinfunction "34_34") (pintype "passive"))
    )
    (net (code "122") (name "Net-(LED3-PadC)") (class "Default")
      (node (ref "LED3") (pin "C") (pinfunction "C_C") (pintype "passive"))
      (node (ref "R1") (pin "2") (pinfunction "2_2") (pintype "passive"))
    )
    (net (code "123") (name "Net-(LED4-PadC)") (class "Default")
      (node (ref "LED4") (pin "C") (pinfunction "C_C") (pintype "passive"))
      (node (ref "R2") (pin "2") (pinfunction "2_2") (pintype "passive"))
    )
    (net (code "124") (name "unconnected-(J13-Pad1)") (class "Default")
      (node (ref "J13") (pin "1") (pinfunction "1_1") (pintype "passive"))
    )
    (net (code "125") (name "unconnected-(J13-Pad2)") (class "Default")
      (node (ref "J13") (pin "2") (pinfunction "2_2") (pintype "passive"))
    )
    (net (code "126") (name "unconnected-(J13-Pad3)") (class "Default")
      (node (ref "J13") (pin "3") (pinfunction "3_3") (pintype "passive"))
    )
    (net (code "127") (name "unconnected-(J13-Pad4)") (class "Default")
      (node (ref "J13") (pin "4") (pinfunction "4_4") (pintype "passive"))
    )
    (net (code "128") (name "unconnected-(J13-Pad5)") (class "Default")
      (node (ref "J13") (pin "5") (pinfunction "5_5") (pintype "passive"))
    )
    (net (code "129") (name "unconnected-(J13-Pad6)") (class "Default")
      (node (ref "J13") (pin "6") (pinfunction "6_6") (pintype "passive"))
    )
    (net (code "130") (name "unconnected-(J14-Pad1)") (class "Default")
      (node (ref "J14") (pin "1") (pinfunction "1_1") (pintype "passive"))
    )
    (net (code "131") (name "unconnected-(J14-Pad2)") (class "Default")
      (node (ref "J14") (pin "2") (pinfunction "2_2") (pintype "passive"))
    )
    (net (code "132") (name "unconnected-(J14-Pad3)") (class "Default")
      (node (ref "J14") (pin "3") (pinfunction "3_3") (pintype "passive"))
    )
    (net (code "133") (name "unconnected-(J14-Pad4)") (class "Default")
      (node (ref "J14") (pin "4") (pinfunction "4_4") (pintype "passive"))
    )
    (net (code "134") (name "unconnected-(J14-Pad5)") (class "Default")
      (node (ref "J14") (pin "5") (pinfunction "5_5") (pintype "passive"))
    )
    (net (code "135") (name "unconnected-(J15-Pad7)") (class "Default")
      (node (ref "J15") (pin "7") (pinfunction "7_7") (pintype "passive"))
    )
    (net (code "136") (name "unconnected-(J15-Pad8)") (class "Default")
      (node (ref "J15") (pin "8") (pinfunction "8_8") (pintype "passive"))
    )
    (net (code "137") (name "unconnected-(J22-Pad6)") (class "Default")
      (node (ref "J22") (pin "6") (pinfunction "6_6") (pintype "passive"))
    )
    (net (code "138") (name "unconnected-(J23-Pad1)") (class "Default")
      (node (ref "J23") (pin "1") (pinfunction "1_1") (pintype "passive"))
    )
    (net (code "139") (name "unconnected-(J23-Pad2)") (class "Default")
      (node (ref "J23") (pin "2") (pinfunction "2_2") (pintype "passive"))
    )
    (net (code "140") (name "unconnected-(J23-Pad3)") (class "Default")
      (node (ref "J23") (pin "3") (pinfunction "3_3") (pintype "passive"))
    )
    (net (code "141") (name "unconnected-(J23-Pad4)") (class "Default")
      (node (ref "J23") (pin "4") (pinfunction "4_4") (pintype "passive"))
    )
    (net (code "142") (name "unconnected-(J23-Pad5)") (class "Default")
      (node (ref "J23") (pin "5") (pinfunction "5_5") (pintype "passive"))
    )
    (net (code "143") (name "unconnected-(J23-Pad6)") (class "Default")
      (node (ref "J23") (pin "6") (pinfunction "6_6") (pintype "passive"))
    )
    (net (code "144") (name "unconnected-(J23-Pad7)") (class "Default")
      (node (ref "J23") (pin "7") (pinfunction "7_7") (pintype "passive"))
    )
    (net (code "145") (name "unconnected-(J23-Pad8)") (class "Default")
      (node (ref "J23") (pin "8") (pinfunction "8_8") (pintype "passive"))
    )
    (net (code "146") (name "unconnected-(J24-Pad1)") (class "Default")
      (node (ref "J24") (pin "1") (pinfunction "1_1") (pintype "passive"))
    )
    (net (code "147") (name "unconnected-(J24-Pad2)") (class "Default")
      (node (ref "J24") (pin "2") (pinfunction "2_2") (pintype "passive"))
    )
    (net (code "148") (name "unconnected-(J24-Pad3)") (class "Default")
      (node (ref "J24") (pin "3") (pinfunction "3_3") (pintype "passive"))
    )
    (net (code "149") (name "unconnected-(J24-Pad4)") (class "Default")
      (node (ref "J24") (pin "4") (pinfunction "4_4") (pintype "passive"))
    )
    (net (code "150") (name "unconnected-(J24-Pad5)") (class "Default")
      (node (ref "J24") (pin "5") (pinfunction "5_5") (pintype "passive"))
    )
    (net (code "151") (name "unconnected-(J24-Pad6)") (class "Default")
      (node (ref "J24") (pin "6") (pinfunction "6_6") (pintype "passive"))
    )
    (net (code "152") (name "~{RESET}") (class "Default")
      (node (ref "ICSP") (pin "5") (pinfunction "5_5") (pintype "passive"))
      (node (ref "J10") (pin "1") (pinfunction "1_1") (pintype "passive"))
      (node (ref "J12") (pin "1") (pinfunction "1_1") (pintype "passive"))
      (node (ref "PWR") (pin "1") (pinfunction "1_1") (pintype "passive"))
      (node (ref "R3") (pin "1") (pinfunction "1_1") (pintype "passive"))
      (node (ref "RESET") (pin "3") (pinfunction "P_3") (pintype "passive"))
      (node (ref "RESET") (pin "4") (pinfunction "P1_4") (pintype "passive"))
    )
  )
)
